# motor-shield02.net
KiCad netlist of a schematic drawn in EAGLE
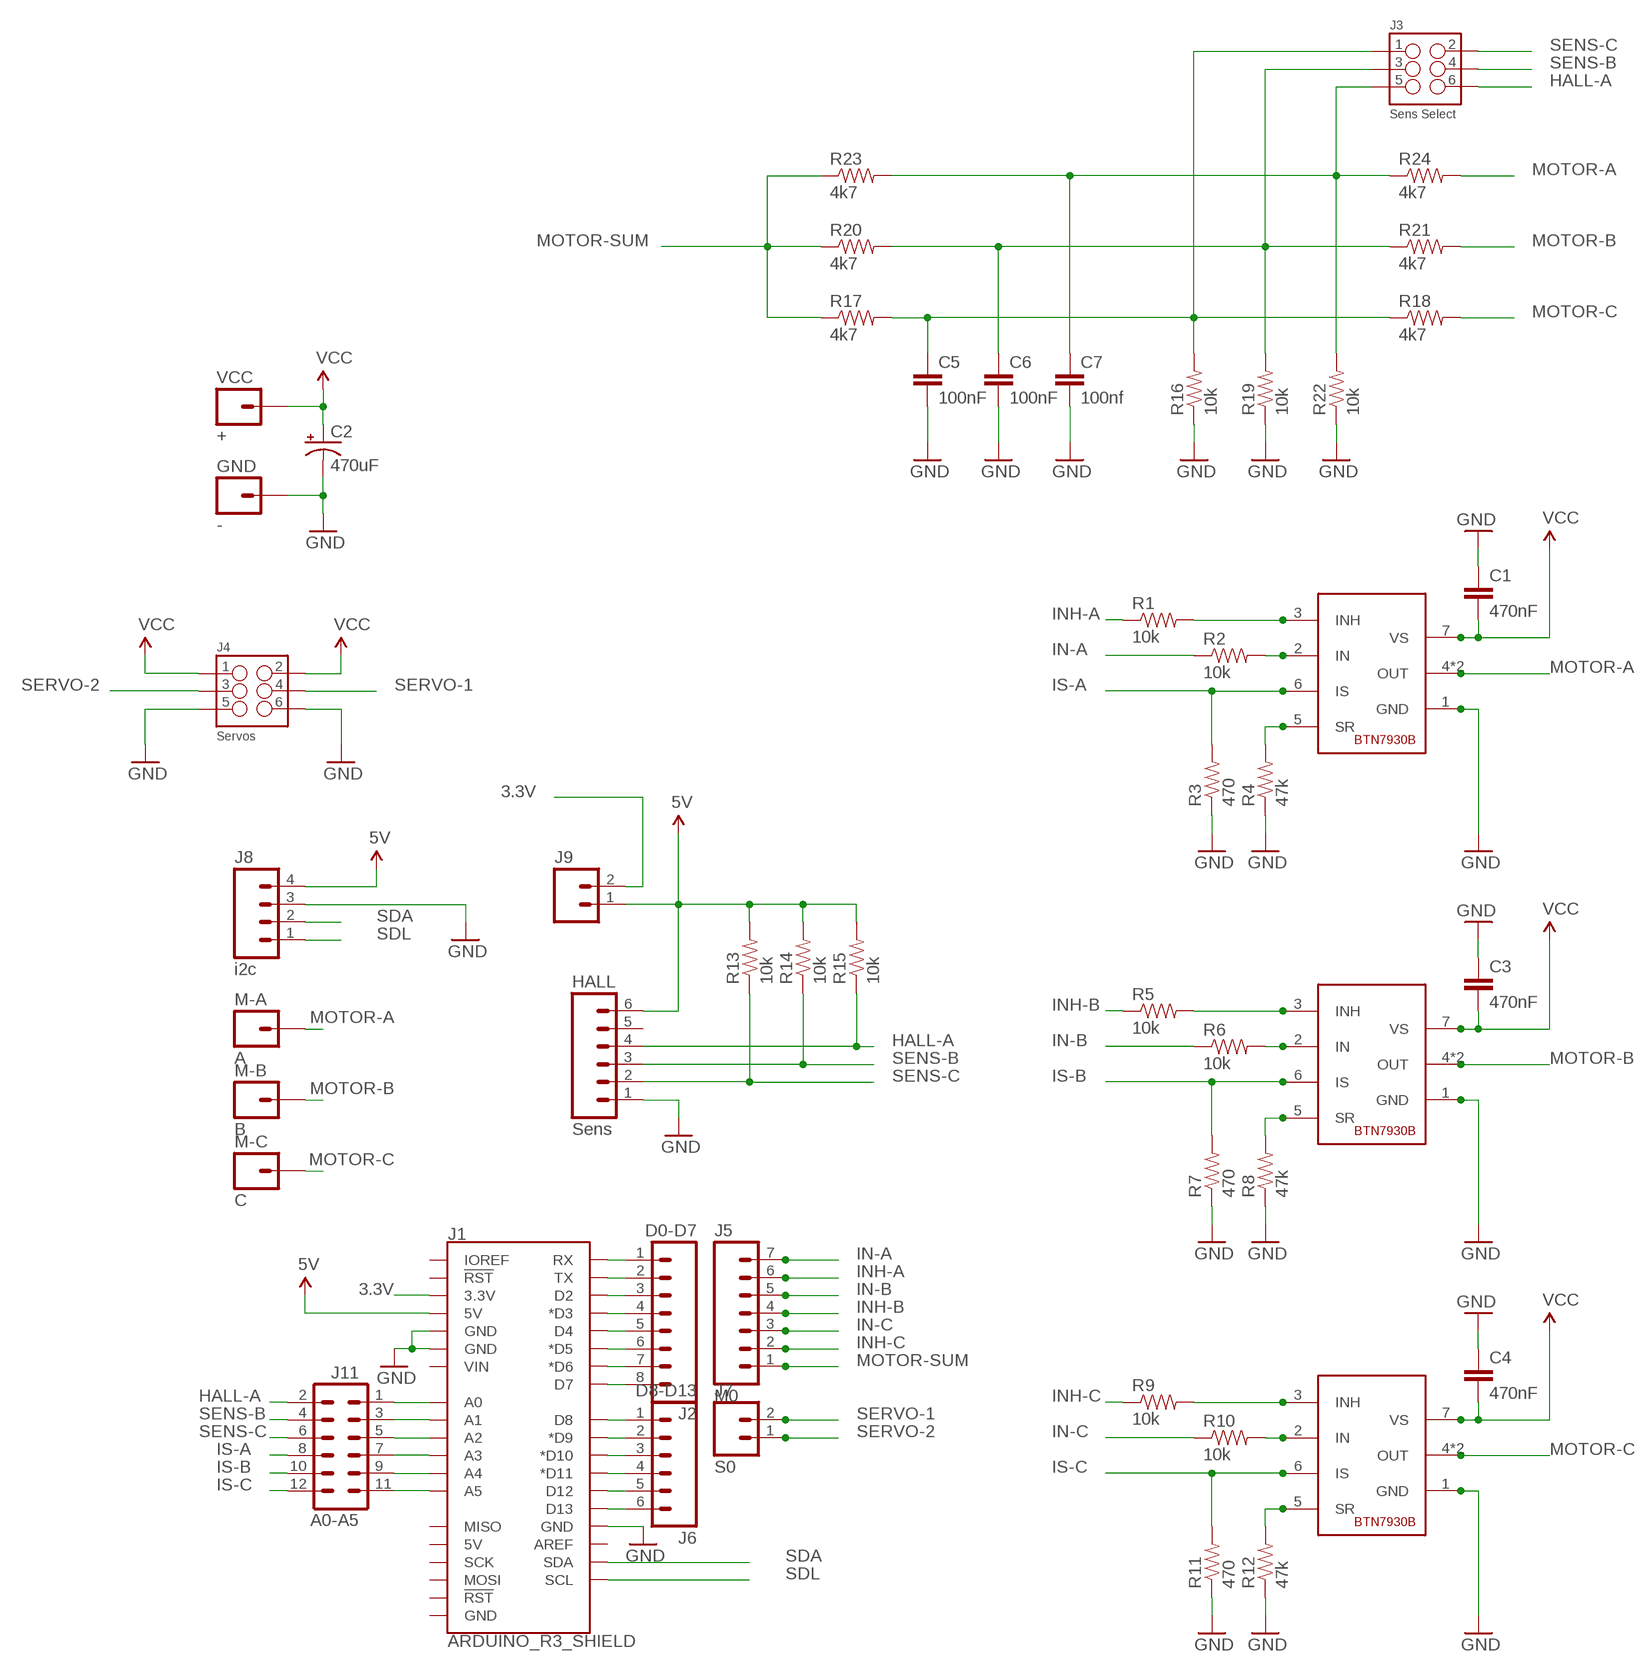
[diagram p0: schematic, sheet 1]

(export (version "E")
  (design (tool "Eeschema 10.0.6"))
  (components
    (comp (ref "C1")
      (value "470nF")
      (footprint "eagle-import:CAP-PTH-SMALLEZ")
      (libsource (lib "eagle-import") (part "CAPEZ"))
    )
    (comp (ref "C2")
      (value "470uF")
      (footprint "eagle-import:CPOL-RADIAL-100UF-25V")
      (libsource (lib "eagle-import") (part "CAP_POLPTH1"))
    )
    (comp (ref "C3")
      (value "470nF")
      (footprint "eagle-import:CAP-PTH-SMALLEZ")
      (libsource (lib "eagle-import") (part "CAPEZ"))
    )
    (comp (ref "C4")
      (value "470nF")
      (footprint "eagle-import:CAP-PTH-SMALLEZ")
      (libsource (lib "eagle-import") (part "CAPEZ"))
    )
    (comp (ref "C5")
      (value "100nF")
      (footprint "eagle-import:CAP-PTH-SMALLEZ")
      (libsource (lib "eagle-import") (part "CAPEZ"))
    )
    (comp (ref "C6")
      (value "100nF")
      (footprint "eagle-import:CAP-PTH-SMALLEZ")
      (libsource (lib "eagle-import") (part "CAPEZ"))
    )
    (comp (ref "C7")
      (value "100nf")
      (footprint "eagle-import:CAP-PTH-SMALLEZ")
      (libsource (lib "eagle-import") (part "CAPEZ"))
    )
    (comp (ref "DA")
      (value "H-Bridge")
      (footprint "eagle-import:INF-PG-TO263-7-1_L_1PRIMARY")
      (libsource (lib "eagle-import") (part "INF-PG-TO263-7-1_L_1"))
    )
    (comp (ref "DB")
      (value "H-Bridge")
      (footprint "eagle-import:INF-PG-TO263-7-1_L_1PRIMARY")
      (libsource (lib "eagle-import") (part "INF-PG-TO263-7-1_L_1"))
    )
    (comp (ref "DC")
      (value "H-Bridge")
      (footprint "eagle-import:INF-PG-TO263-7-1_L_1PRIMARY")
      (libsource (lib "eagle-import") (part "INF-PG-TO263-7-1_L_1"))
    )
    (comp (ref "GND")
      (value "-")
      (footprint "eagle-import:SMTRA-256-8-6")
      (libsource (lib "eagle-import") (part "M01SMTRA-256-8-6"))
    )
    (comp (ref "HALL")
      (value "Sens")
      (footprint "eagle-import:1X06-1MM")
      (libsource (lib "eagle-import") (part "M06SMD-1MM"))
    )
    (comp (ref "J1")
      (value "ARDUINO_R3_SHIELD")
      (footprint "eagle-import:UNO_R3_SHIELD_ICSP")
      (libsource (lib "eagle-import") (part "ARDUINO_R3_SHIELD_ICSP"))
    )
    (comp (ref "J2")
      (value "D0-D7")
      (footprint "eagle-import:1X08_NO_SILK")
      (libsource (lib "eagle-import") (part "M08NO_SILK_FEMALE_PTH"))
    )
    (comp (ref "J3")
      (value "Sens Select")
      (footprint "eagle-import:2X3")
      (libsource (lib "eagle-import") (part "M03X2FEMALE"))
    )
    (comp (ref "J4")
      (value "Servos")
      (footprint "eagle-import:2X3")
      (libsource (lib "eagle-import") (part "M03X2FEMALE"))
    )
    (comp (ref "J5")
      (value "M0")
      (footprint "eagle-import:1X07_NO_SILK")
      (libsource (lib "eagle-import") (part "M07NO_SILK"))
    )
    (comp (ref "J6")
      (value "D8-D13")
      (footprint "eagle-import:1X06_NO_SILK_YES_STOP")
      (libsource (lib "eagle-import") (part "M06NO_SILK_YES_STOP"))
    )
    (comp (ref "J7")
      (value "S0")
      (footprint "eagle-import:1X02_NO_SILK")
      (libsource (lib "eagle-import") (part "M021X02_NO_SILK"))
    )
    (comp (ref "J8")
      (value "i2c")
      (footprint "eagle-import:1X04_NO_SILK_ALL_ROUND")
      (libsource (lib "eagle-import") (part "M04NO_SILK_ALL_ROUND"))
    )
    (comp (ref "J9")
      (value "M021X02_NO_SILK")
      (footprint "eagle-import:1X02_NO_SILK")
      (libsource (lib "eagle-import") (part "M021X02_NO_SILK"))
    )
    (comp (ref "J11")
      (value "A0-A5")
      (footprint "eagle-import:2X6")
      (libsource (lib "eagle-import") (part "M06X2PTH_FEMALE"))
    )
    (comp (ref "M-A")
      (value "A")
      (footprint "eagle-import:SMTRA-256-8-6")
      (libsource (lib "eagle-import") (part "M01SMTRA-256-8-6"))
    )
    (comp (ref "M-B")
      (value "B")
      (footprint "eagle-import:SMTRA-256-8-6")
      (libsource (lib "eagle-import") (part "M01SMTRA-256-8-6"))
    )
    (comp (ref "M-C")
      (value "C")
      (footprint "eagle-import:SMTRA-256-8-6")
      (libsource (lib "eagle-import") (part "M01SMTRA-256-8-6"))
    )
    (comp (ref "R1")
      (value "10k")
      (footprint "eagle-import:AXIAL-0.3")
      (libsource (lib "eagle-import") (part "10KOHM-1/4W-1%(PTH)HORIZ"))
    )
    (comp (ref "R2")
      (value "10k")
      (footprint "eagle-import:AXIAL-0.3")
      (libsource (lib "eagle-import") (part "10KOHM-1/4W-1%(PTH)HORIZ"))
    )
    (comp (ref "R3")
      (value "470")
      (footprint "eagle-import:AXIAL-0.3")
      (libsource (lib "eagle-import") (part "10KOHM-1/4W-1%(PTH)HORIZ"))
    )
    (comp (ref "R4")
      (value "47k")
      (footprint "eagle-import:AXIAL-0.3")
      (libsource (lib "eagle-import") (part "10KOHM-1/4W-1%(PTH)HORIZ"))
    )
    (comp (ref "R5")
      (value "10k")
      (footprint "eagle-import:AXIAL-0.3")
      (libsource (lib "eagle-import") (part "10KOHM-1/4W-1%(PTH)HORIZ"))
    )
    (comp (ref "R6")
      (value "10k")
      (footprint "eagle-import:AXIAL-0.3")
      (libsource (lib "eagle-import") (part "10KOHM-1/4W-1%(PTH)HORIZ"))
    )
    (comp (ref "R7")
      (value "470")
      (footprint "eagle-import:AXIAL-0.3")
      (libsource (lib "eagle-import") (part "10KOHM-1/4W-1%(PTH)HORIZ"))
    )
    (comp (ref "R8")
      (value "47k")
      (footprint "eagle-import:AXIAL-0.3")
      (libsource (lib "eagle-import") (part "10KOHM-1/4W-1%(PTH)HORIZ"))
    )
    (comp (ref "R9")
      (value "10k")
      (footprint "eagle-import:AXIAL-0.3")
      (libsource (lib "eagle-import") (part "10KOHM-1/4W-1%(PTH)HORIZ"))
    )
    (comp (ref "R10")
      (value "10k")
      (footprint "eagle-import:AXIAL-0.3")
      (libsource (lib "eagle-import") (part "10KOHM-1/4W-1%(PTH)HORIZ"))
    )
    (comp (ref "R11")
      (value "470")
      (footprint "eagle-import:AXIAL-0.3")
      (libsource (lib "eagle-import") (part "10KOHM-1/4W-1%(PTH)HORIZ"))
    )
    (comp (ref "R12")
      (value "47k")
      (footprint "eagle-import:AXIAL-0.3")
      (libsource (lib "eagle-import") (part "10KOHM-1/4W-1%(PTH)HORIZ"))
    )
    (comp (ref "R13")
      (value "10k")
      (footprint "eagle-import:AXIAL-0.3")
      (libsource (lib "eagle-import") (part "10KOHM-1/4W-1%(PTH)HORIZ"))
    )
    (comp (ref "R14")
      (value "10k")
      (footprint "eagle-import:AXIAL-0.3")
      (libsource (lib "eagle-import") (part "10KOHM-1/4W-1%(PTH)HORIZ"))
    )
    (comp (ref "R15")
      (value "10k")
      (footprint "eagle-import:AXIAL-0.3")
      (libsource (lib "eagle-import") (part "10KOHM-1/4W-1%(PTH)HORIZ"))
    )
    (comp (ref "R16")
      (value "10k")
      (footprint "eagle-import:AXIAL-0.3")
      (libsource (lib "eagle-import") (part "10KOHM-1/4W-1%(PTH)HORIZ"))
    )
    (comp (ref "R17")
      (value "4k7")
      (footprint "eagle-import:AXIAL-0.3")
      (libsource (lib "eagle-import") (part "10KOHM-1/4W-1%(PTH)HORIZ"))
    )
    (comp (ref "R18")
      (value "4k7")
      (footprint "eagle-import:AXIAL-0.3")
      (libsource (lib "eagle-import") (part "10KOHM-1/4W-1%(PTH)HORIZ"))
    )
    (comp (ref "R19")
      (value "10k")
      (footprint "eagle-import:AXIAL-0.3")
      (libsource (lib "eagle-import") (part "10KOHM-1/4W-1%(PTH)HORIZ"))
    )
    (comp (ref "R20")
      (value "4k7")
      (footprint "eagle-import:AXIAL-0.3")
      (libsource (lib "eagle-import") (part "10KOHM-1/4W-1%(PTH)HORIZ"))
    )
    (comp (ref "R21")
      (value "4k7")
      (footprint "eagle-import:AXIAL-0.3")
      (libsource (lib "eagle-import") (part "10KOHM-1/4W-1%(PTH)HORIZ"))
    )
    (comp (ref "R22")
      (value "10k")
      (footprint "eagle-import:AXIAL-0.3")
      (libsource (lib "eagle-import") (part "10KOHM-1/4W-1%(PTH)HORIZ"))
    )
    (comp (ref "R23")
      (value "4k7")
      (footprint "eagle-import:AXIAL-0.3")
      (libsource (lib "eagle-import") (part "10KOHM-1/4W-1%(PTH)HORIZ"))
    )
    (comp (ref "R24")
      (value "4k7")
      (footprint "eagle-import:AXIAL-0.3")
      (libsource (lib "eagle-import") (part "10KOHM-1/4W-1%(PTH)HORIZ"))
    )
    (comp (ref "VCC")
      (value "+")
      (footprint "eagle-import:SMTRA-256-8-6")
      (libsource (lib "eagle-import") (part "M01SMTRA-256-8-6"))
    )
  )
  (nets
    (net (code "1") (name "/3.3V") (class "Default")
      (node (ref "J1") (pin "3.3V") (pinfunction "3.3V_3.3V") (pintype "bidirectional"))
      (node (ref "J9") (pin "2") (pinfunction "2_2") (pintype "passive"))
    )
    (net (code "2") (name "/HALL-A") (class "Default")
      (node (ref "HALL") (pin "4") (pinfunction "4_4") (pintype "passive"))
      (node (ref "J11") (pin "2") (pinfunction "2_2") (pintype "passive"))
      (node (ref "J3") (pin "6") (pinfunction "6_6") (pintype "bidirectional"))
      (node (ref "R15") (pin "P$1") (pinfunction "1_P$1") (pintype "passive"))
    )
    (net (code "3") (name "/IN-A") (class "Default")
      (node (ref "J5") (pin "7") (pinfunction "7_7") (pintype "passive"))
      (node (ref "R2") (pin "P$1") (pinfunction "1_P$1") (pintype "passive"))
    )
    (net (code "4") (name "/IN-B") (class "Default")
      (node (ref "J5") (pin "5") (pinfunction "5_5") (pintype "passive"))
      (node (ref "R6") (pin "P$1") (pinfunction "1_P$1") (pintype "passive"))
    )
    (net (code "5") (name "/IN-C") (class "Default")
      (node (ref "J5") (pin "3") (pinfunction "3_3") (pintype "passive"))
      (node (ref "R10") (pin "P$1") (pinfunction "1_P$1") (pintype "passive"))
    )
    (net (code "6") (name "/INH-A") (class "Default")
      (node (ref "J5") (pin "6") (pinfunction "6_6") (pintype "passive"))
      (node (ref "R1") (pin "P$1") (pinfunction "1_P$1") (pintype "passive"))
    )
    (net (code "7") (name "/INH-B") (class "Default")
      (node (ref "J5") (pin "4") (pinfunction "4_4") (pintype "passive"))
      (node (ref "R5") (pin "P$1") (pinfunction "1_P$1") (pintype "passive"))
    )
    (net (code "8") (name "/INH-C") (class "Default")
      (node (ref "J5") (pin "2") (pinfunction "2_2") (pintype "passive"))
      (node (ref "R9") (pin "P$1") (pinfunction "1_P$1") (pintype "passive"))
    )
    (net (code "9") (name "/IS-A") (class "Default")
      (node (ref "DA") (pin "6") (pinfunction "IS_6") (pintype "bidirectional"))
      (node (ref "J11") (pin "8") (pinfunction "8_8") (pintype "passive"))
      (node (ref "R3") (pin "P$2") (pinfunction "2_P$2") (pintype "passive"))
    )
    (net (code "10") (name "/IS-B") (class "Default")
      (node (ref "DB") (pin "6") (pinfunction "IS_6") (pintype "bidirectional"))
      (node (ref "J11") (pin "10") (pinfunction "10_10") (pintype "passive"))
      (node (ref "R7") (pin "P$2") (pinfunction "2_P$2") (pintype "passive"))
    )
    (net (code "11") (name "/IS-C") (class "Default")
      (node (ref "DC") (pin "6") (pinfunction "IS_6") (pintype "bidirectional"))
      (node (ref "J11") (pin "12") (pinfunction "12_12") (pintype "passive"))
      (node (ref "R11") (pin "P$2") (pinfunction "2_P$2") (pintype "passive"))
    )
    (net (code "12") (name "/MOTOR-A") (class "Default")
      (node (ref "DA") (pin "4") (pinfunction "OUT_4") (pintype "bidirectional"))
      (node (ref "DA") (pin "8") (pinfunction "OUT_8") (pintype "bidirectional"))
      (node (ref "M-A") (pin "P$1") (pinfunction "1_P$1") (pintype "passive"))
      (node (ref "R24") (pin "P$2") (pinfunction "2_P$2") (pintype "passive"))
    )
    (net (code "13") (name "/MOTOR-B") (class "Default")
      (node (ref "DB") (pin "4") (pinfunction "OUT_4") (pintype "bidirectional"))
      (node (ref "DB") (pin "8") (pinfunction "OUT_8") (pintype "bidirectional"))
      (node (ref "M-B") (pin "P$1") (pinfunction "1_P$1") (pintype "passive"))
      (node (ref "R21") (pin "P$2") (pinfunction "2_P$2") (pintype "passive"))
    )
    (net (code "14") (name "/MOTOR-C") (class "Default")
      (node (ref "DC") (pin "4") (pinfunction "OUT_4") (pintype "bidirectional"))
      (node (ref "DC") (pin "8") (pinfunction "OUT_8") (pintype "bidirectional"))
      (node (ref "M-C") (pin "P$1") (pinfunction "1_P$1") (pintype "passive"))
      (node (ref "R18") (pin "P$2") (pinfunction "2_P$2") (pintype "passive"))
    )
    (net (code "15") (name "/MOTOR-SUM") (class "Default")
      (node (ref "J5") (pin "1") (pinfunction "1_1") (pintype "passive"))
      (node (ref "R17") (pin "P$1") (pinfunction "1_P$1") (pintype "passive"))
      (node (ref "R20") (pin "P$1") (pinfunction "1_P$1") (pintype "passive"))
      (node (ref "R23") (pin "P$1") (pinfunction "1_P$1") (pintype "passive"))
    )
    (net (code "16") (name "/SDA") (class "Default")
      (node (ref "J1") (pin "SDA") (pinfunction "SDA_SDA") (pintype "bidirectional"))
      (node (ref "J8") (pin "2") (pinfunction "2_2") (pintype "passive"))
    )
    (net (code "17") (name "/SDL") (class "Default")
      (node (ref "J1") (pin "SCL") (pinfunction "SCL_SCL") (pintype "bidirectional"))
      (node (ref "J8") (pin "1") (pinfunction "1_1") (pintype "passive"))
    )
    (net (code "18") (name "/SENS-B") (class "Default")
      (node (ref "HALL") (pin "3") (pinfunction "3_3") (pintype "passive"))
      (node (ref "J11") (pin "4") (pinfunction "4_4") (pintype "passive"))
      (node (ref "J3") (pin "4") (pinfunction "4_4") (pintype "bidirectional"))
      (node (ref "R14") (pin "P$1") (pinfunction "1_P$1") (pintype "passive"))
    )
    (net (code "19") (name "/SENS-C") (class "Default")
      (node (ref "HALL") (pin "2") (pinfunction "2_2") (pintype "passive"))
      (node (ref "J11") (pin "6") (pinfunction "6_6") (pintype "passive"))
      (node (ref "J3") (pin "2") (pinfunction "2_2") (pintype "bidirectional"))
      (node (ref "R13") (pin "P$1") (pinfunction "1_P$1") (pintype "passive"))
    )
    (net (code "20") (name "/SERVO-1") (class "Default")
      (node (ref "J4") (pin "4") (pinfunction "4_4") (pintype "bidirectional"))
      (node (ref "J7") (pin "2") (pinfunction "2_2") (pintype "passive"))
    )
    (net (code "21") (name "/SERVO-2") (class "Default")
      (node (ref "J4") (pin "3") (pinfunction "3_3") (pintype "bidirectional"))
      (node (ref "J7") (pin "1") (pinfunction "1_1") (pintype "passive"))
    )
    (net (code "22") (name "5V") (class "Default")
      (node (ref "HALL") (pin "6") (pinfunction "6_6") (pintype "passive"))
      (node (ref "J1") (pin "5V") (pinfunction "5V_5V") (pintype "bidirectional"))
      (node (ref "J8") (pin "4") (pinfunction "4_4") (pintype "passive"))
      (node (ref "J9") (pin "1") (pinfunction "1_1") (pintype "passive"))
      (node (ref "R13") (pin "P$2") (pinfunction "2_P$2") (pintype "passive"))
      (node (ref "R14") (pin "P$2") (pinfunction "2_P$2") (pintype "passive"))
      (node (ref "R15") (pin "P$2") (pinfunction "2_P$2") (pintype "passive"))
    )
    (net (code "23") (name "GND") (class "Default")
      (node (ref "C1") (pin "1") (pinfunction "1_1") (pintype "passive"))
      (node (ref "C2") (pin "2") (pinfunction "-_2") (pintype "passive"))
      (node (ref "C3") (pin "1") (pinfunction "1_1") (pintype "passive"))
      (node (ref "C4") (pin "1") (pinfunction "1_1") (pintype "passive"))
      (node (ref "C5") (pin "2") (pinfunction "2_2") (pintype "passive"))
      (node (ref "C6") (pin "2") (pinfunction "2_2") (pintype "passive"))
      (node (ref "C7") (pin "2") (pinfunction "2_2") (pintype "passive"))
      (node (ref "DA") (pin "1") (pinfunction "GND_1") (pintype "bidirectional"))
      (node (ref "DB") (pin "1") (pinfunction "GND_1") (pintype "bidirectional"))
      (node (ref "DC") (pin "1") (pinfunction "GND_1") (pintype "bidirectional"))
      (node (ref "GND") (pin "P$1") (pinfunction "1_P$1") (pintype "passive"))
      (node (ref "HALL") (pin "1") (pinfunction "1_1") (pintype "passive"))
      (node (ref "J1") (pin "GND@0") (pinfunction "GND_GND@0") (pintype "bidirectional"))
      (node (ref "J1") (pin "GND@1") (pinfunction "GND_GND@1") (pintype "bidirectional"))
      (node (ref "J1") (pin "GND@2") (pinfunction "GND_GND@2") (pintype "bidirectional"))
      (node (ref "J4") (pin "5") (pinfunction "5_5") (pintype "bidirectional"))
      (node (ref "J4") (pin "6") (pinfunction "6_6") (pintype "bidirectional"))
      (node (ref "J8") (pin "3") (pinfunction "3_3") (pintype "passive"))
      (node (ref "R11") (pin "P$1") (pinfunction "1_P$1") (pintype "passive"))
      (node (ref "R12") (pin "P$1") (pinfunction "1_P$1") (pintype "passive"))
      (node (ref "R16") (pin "P$1") (pinfunction "1_P$1") (pintype "passive"))
      (node (ref "R19") (pin "P$1") (pinfunction "1_P$1") (pintype "passive"))
      (node (ref "R22") (pin "P$1") (pinfunction "1_P$1") (pintype "passive"))
      (node (ref "R3") (pin "P$1") (pinfunction "1_P$1") (pintype "passive"))
      (node (ref "R4") (pin "P$1") (pinfunction "1_P$1") (pintype "passive"))
      (node (ref "R7") (pin "P$1") (pinfunction "1_P$1") (pintype "passive"))
      (node (ref "R8") (pin "P$1") (pinfunction "1_P$1") (pintype "passive"))
    )
    (net (code "24") (name "Net-(DA-IN)") (class "Default")
      (node (ref "DA") (pin "2") (pinfunction "IN_2") (pintype "bidirectional"))
      (node (ref "R2") (pin "P$2") (pinfunction "2_P$2") (pintype "passive"))
    )
    (net (code "25") (name "Net-(DA-INH)") (class "Default")
      (node (ref "DA") (pin "3") (pinfunction "INH_3") (pintype "bidirectional"))
      (node (ref "R1") (pin "P$2") (pinfunction "2_P$2") (pintype "passive"))
    )
    (net (code "26") (name "Net-(DA-SR)") (class "Default")
      (node (ref "DA") (pin "5") (pinfunction "SR_5") (pintype "bidirectional"))
      (node (ref "R4") (pin "P$2") (pinfunction "2_P$2") (pintype "passive"))
    )
    (net (code "27") (name "Net-(DB-IN)") (class "Default")
      (node (ref "DB") (pin "2") (pinfunction "IN_2") (pintype "bidirectional"))
      (node (ref "R6") (pin "P$2") (pinfunction "2_P$2") (pintype "passive"))
    )
    (net (code "28") (name "Net-(DB-INH)") (class "Default")
      (node (ref "DB") (pin "3") (pinfunction "INH_3") (pintype "bidirectional"))
      (node (ref "R5") (pin "P$2") (pinfunction "2_P$2") (pintype "passive"))
    )
    (net (code "29") (name "Net-(DB-SR)") (class "Default")
      (node (ref "DB") (pin "5") (pinfunction "SR_5") (pintype "bidirectional"))
      (node (ref "R8") (pin "P$2") (pinfunction "2_P$2") (pintype "passive"))
    )
    (net (code "30") (name "Net-(DC-IN)") (class "Default")
      (node (ref "DC") (pin "2") (pinfunction "IN_2") (pintype "bidirectional"))
      (node (ref "R10") (pin "P$2") (pinfunction "2_P$2") (pintype "passive"))
    )
    (net (code "31") (name "Net-(DC-INH)") (class "Default")
      (node (ref "DC") (pin "3") (pinfunction "INH_3") (pintype "bidirectional"))
      (node (ref "R9") (pin "P$2") (pinfunction "2_P$2") (pintype "passive"))
    )
    (net (code "32") (name "Net-(DC-SR)") (class "Default")
      (node (ref "DC") (pin "5") (pinfunction "SR_5") (pintype "bidirectional"))
      (node (ref "R12") (pin "P$2") (pinfunction "2_P$2") (pintype "passive"))
    )
    (net (code "33") (name "Net-(J1-*D3)") (class "Default")
      (node (ref "J1") (pin "D3") (pinfunction "*D3_D3") (pintype "bidirectional"))
      (node (ref "J2") (pin "4") (pinfunction "4_4") (pintype "passive"))
    )
    (net (code "34") (name "Net-(J1-*D5)") (class "Default")
      (node (ref "J1") (pin "D5") (pinfunction "*D5_D5") (pintype "bidirectional"))
      (node (ref "J2") (pin "6") (pinfunction "6_6") (pintype "passive"))
    )
    (net (code "35") (name "Net-(J1-*D6)") (class "Default")
      (node (ref "J1") (pin "D6") (pinfunction "*D6_D6") (pintype "bidirectional"))
      (node (ref "J2") (pin "7") (pinfunction "7_7") (pintype "passive"))
    )
    (net (code "36") (name "Net-(J1-*D9)") (class "Default")
      (node (ref "J1") (pin "D9") (pinfunction "*D9_D9") (pintype "bidirectional"))
      (node (ref "J6") (pin "2") (pinfunction "2_2") (pintype "passive"))
    )
    (net (code "37") (name "Net-(J1-*D10)") (class "Default")
      (node (ref "J1") (pin "D10") (pinfunction "*D10_D10") (pintype "bidirectional"))
      (node (ref "J6") (pin "3") (pinfunction "3_3") (pintype "passive"))
    )
    (net (code "38") (name "Net-(J1-*D11)") (class "Default")
      (node (ref "J1") (pin "D11") (pinfunction "*D11_D11") (pintype "bidirectional"))
      (node (ref "J6") (pin "4") (pinfunction "4_4") (pintype "passive"))
    )
    (net (code "39") (name "Net-(J1-PadA0)") (class "Default")
      (node (ref "J1") (pin "A0") (pinfunction "A0_A0") (pintype "bidirectional"))
      (node (ref "J11") (pin "1") (pinfunction "1_1") (pintype "passive"))
    )
    (net (code "40") (name "Net-(J1-PadA1)") (class "Default")
      (node (ref "J1") (pin "A1") (pinfunction "A1_A1") (pintype "bidirectional"))
      (node (ref "J11") (pin "3") (pinfunction "3_3") (pintype "passive"))
    )
    (net (code "41") (name "Net-(J1-PadA2)") (class "Default")
      (node (ref "J1") (pin "A2") (pinfunction "A2_A2") (pintype "bidirectional"))
      (node (ref "J11") (pin "5") (pinfunction "5_5") (pintype "passive"))
    )
    (net (code "42") (name "Net-(J1-PadA3)") (class "Default")
      (node (ref "J1") (pin "A3") (pinfunction "A3_A3") (pintype "bidirectional"))
      (node (ref "J11") (pin "7") (pinfunction "7_7") (pintype "passive"))
    )
    (net (code "43") (name "Net-(J1-PadA4)") (class "Default")
      (node (ref "J1") (pin "A4") (pinfunction "A4_A4") (pintype "bidirectional"))
      (node (ref "J11") (pin "9") (pinfunction "9_9") (pintype "passive"))
    )
    (net (code "44") (name "Net-(J1-PadA5)") (class "Default")
      (node (ref "J1") (pin "A5") (pinfunction "A5_A5") (pintype "bidirectional"))
      (node (ref "J11") (pin "11") (pinfunction "11_11") (pintype "passive"))
    )
    (net (code "45") (name "Net-(J1-PadD2)") (class "Default")
      (node (ref "J1") (pin "D2") (pinfunction "D2_D2") (pintype "bidirectional"))
      (node (ref "J2") (pin "3") (pinfunction "3_3") (pintype "passive"))
    )
    (net (code "46") (name "Net-(J1-PadD4)") (class "Default")
      (node (ref "J1") (pin "D4") (pinfunction "D4_D4") (pintype "bidirectional"))
      (node (ref "J2") (pin "5") (pinfunction "5_5") (pintype "passive"))
    )
    (net (code "47") (name "Net-(J1-PadD7)") (class "Default")
      (node (ref "J1") (pin "D7") (pinfunction "D7_D7") (pintype "bidirectional"))
      (node (ref "J2") (pin "8") (pinfunction "8_8") (pintype "passive"))
    )
    (net (code "48") (name "Net-(J1-PadD8)") (class "Default")
      (node (ref "J1") (pin "D8") (pinfunction "D8_D8") (pintype "bidirectional"))
      (node (ref "J6") (pin "1") (pinfunction "1_1") (pintype "passive"))
    )
    (net (code "49") (name "Net-(J1-PadD12)") (class "Default")
      (node (ref "J1") (pin "D12") (pinfunction "D12_D12") (pintype "bidirectional"))
      (node (ref "J6") (pin "5") (pinfunction "5_5") (pintype "passive"))
    )
    (net (code "50") (name "Net-(J1-PadD13)") (class "Default")
      (node (ref "J1") (pin "D13") (pinfunction "D13_D13") (pintype "bidirectional"))
      (node (ref "J6") (pin "6") (pinfunction "6_6") (pintype "passive"))
    )
    (net (code "51") (name "Net-(J1-PadRX)") (class "Default")
      (node (ref "J1") (pin "RX") (pinfunction "RX_RX") (pintype "bidirectional"))
      (node (ref "J2") (pin "1") (pinfunction "1_1") (pintype "passive"))
    )
    (net (code "52") (name "Net-(J1-PadTX)") (class "Default")
      (node (ref "J1") (pin "TX") (pinfunction "TX_TX") (pintype "bidirectional"))
      (node (ref "J2") (pin "2") (pinfunction "2_2") (pintype "passive"))
    )
    (net (code "53") (name "Net-(R16-2)") (class "Default")
      (node (ref "C5") (pin "1") (pinfunction "1_1") (pintype "passive"))
      (node (ref "J3") (pin "1") (pinfunction "1_1") (pintype "bidirectional"))
      (node (ref "R16") (pin "P$2") (pinfunction "2_P$2") (pintype "passive"))
      (node (ref "R17") (pin "P$2") (pinfunction "2_P$2") (pintype "passive"))
      (node (ref "R18") (pin "P$1") (pinfunction "1_P$1") (pintype "passive"))
    )
    (net (code "54") (name "Net-(R19-2)") (class "Default")
      (node (ref "C6") (pin "1") (pinfunction "1_1") (pintype "passive"))
      (node (ref "J3") (pin "3") (pinfunction "3_3") (pintype "bidirectional"))
      (node (ref "R19") (pin "P$2") (pinfunction "2_P$2") (pintype "passive"))
      (node (ref "R20") (pin "P$2") (pinfunction "2_P$2") (pintype "passive"))
      (node (ref "R21") (pin "P$1") (pinfunction "1_P$1") (pintype "passive"))
    )
    (net (code "55") (name "Net-(R22-2)") (class "Default")
      (node (ref "C7") (pin "1") (pinfunction "1_1") (pintype "passive"))
      (node (ref "J3") (pin "5") (pinfunction "5_5") (pintype "bidirectional"))
      (node (ref "R22") (pin "P$2") (pinfunction "2_P$2") (pintype "passive"))
      (node (ref "R23") (pin "P$2") (pinfunction "2_P$2") (pintype "passive"))
      (node (ref "R24") (pin "P$1") (pinfunction "1_P$1") (pintype "passive"))
    )
    (net (code "56") (name "VCC") (class "Default")
      (node (ref "C1") (pin "2") (pinfunction "2_2") (pintype "passive"))
      (node (ref "C2") (pin "1") (pinfunction "+_1") (pintype "passive"))
      (node (ref "C3") (pin "2") (pinfunction "2_2") (pintype "passive"))
      (node (ref "C4") (pin "2") (pinfunction "2_2") (pintype "passive"))
      (node (ref "DA") (pin "7") (pinfunction "VS_7") (pintype "bidirectional"))
      (node (ref "DB") (pin "7") (pinfunction "VS_7") (pintype "bidirectional"))
      (node (ref "DC") (pin "7") (pinfunction "VS_7") (pintype "bidirectional"))
      (node (ref "J4") (pin "1") (pinfunction "1_1") (pintype "bidirectional"))
      (node (ref "J4") (pin "2") (pinfunction "2_2") (pintype "bidirectional"))
      (node (ref "VCC") (pin "P$1") (pinfunction "1_P$1") (pintype "passive"))
    )
    (net (code "57") (name "unconnected-(HALL-Pad5)") (class "Default")
      (node (ref "HALL") (pin "5") (pinfunction "5_5") (pintype "passive"))
    )
    (net (code "58") (name "unconnected-(J1-5V-Pad5V_ICSP)") (class "Default")
      (node (ref "J1") (pin "5V_ICSP") (pinfunction "5V_5V_ICSP") (pintype "bidirectional"))
    )
    (net (code "59") (name "unconnected-(J1-GND-PadGND_ICSP)") (class "Default")
      (node (ref "J1") (pin "GND_ICSP") (pinfunction "GND_GND_ICSP") (pintype "bidirectional"))
    )
    (net (code "60") (name "unconnected-(J1-PadAREF)") (class "Default")
      (node (ref "J1") (pin "AREF") (pinfunction "AREF_AREF") (pintype "bidirectional"))
    )
    (net (code "61") (name "unconnected-(J1-PadIOREF)") (class "Default")
      (node (ref "J1") (pin "IOREF") (pinfunction "IOREF_IOREF") (pintype "bidirectional"))
    )
    (net (code "62") (name "unconnected-(J1-PadMISO)") (class "Default")
      (node (ref "J1") (pin "MISO") (pinfunction "MISO_MISO") (pintype "bidirectional"))
    )
    (net (code "63") (name "unconnected-(J1-PadMOSI)") (class "Default")
      (node (ref "J1") (pin "MOSI") (pinfunction "MOSI_MOSI") (pintype "bidirectional"))
    )
    (net (code "64") (name "unconnected-(J1-PadSCK)") (class "Default")
      (node (ref "J1") (pin "SCK") (pinfunction "SCK_SCK") (pintype "bidirectional"))
    )
    (net (code "65") (name "unconnected-(J1-PadVIN)") (class "Default")
      (node (ref "J1") (pin "VIN") (pinfunction "VIN_VIN") (pintype "bidirectional"))
    )
    (net (code "66") (name "unconnected-(J1-~{RST}-PadRES)") (class "Default")
      (node (ref "J1") (pin "RES") (pinfunction "~{RST}_RES") (pintype "bidirectional"))
    )
    (net (code "67") (name "unconnected-(J1-~{RST}-PadRST_ICSP)") (class "Default")
      (node (ref "J1") (pin "RST_ICSP") (pinfunction "~{RST}_RST_ICSP") (pintype "bidirectional"))
    )
  )
)
